# NT1066_Discovery.net
KiCad netlist of a schematic drawn in EAGLE
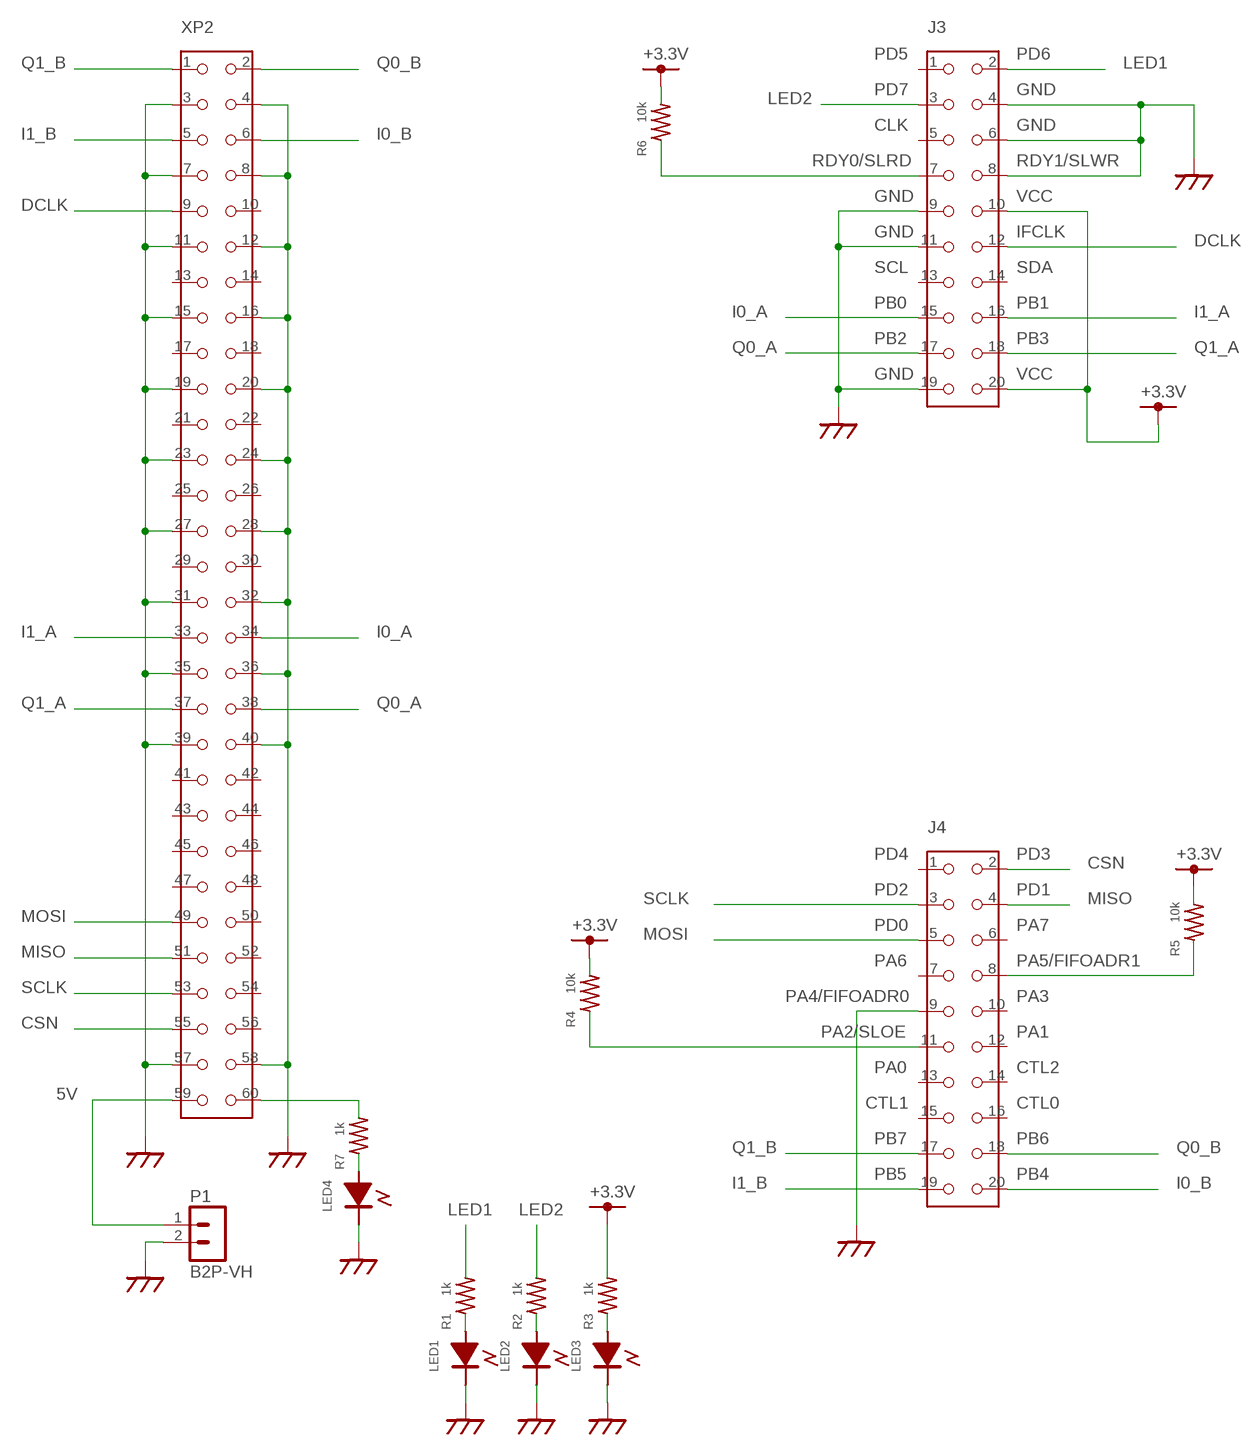
[diagram p0: schematic, sheet 1]

(export (version "E")
  (design (tool "Eeschema 10.0.6"))
  (components
    (comp (ref "J3")
      (value "PINH-2.54MM-20P")
      (footprint "eagle-import:PINH-2.54MM-20P")
      (libsource (lib "eagle-import") (part "PINH-2.54MM-20P"))
    )
    (comp (ref "J4")
      (value "PINH-2.54MM-20P")
      (footprint "eagle-import:PINH-2.54MM-20P")
      (libsource (lib "eagle-import") (part "PINH-2.54MM-20P"))
    )
    (comp (ref "LED1")
      (value "LED1608")
      (footprint "eagle-import:LED_1608")
      (libsource (lib "eagle-import") (part "LED1608"))
    )
    (comp (ref "LED2")
      (value "LED1608")
      (footprint "eagle-import:LED_1608")
      (libsource (lib "eagle-import") (part "LED1608"))
    )
    (comp (ref "LED3")
      (value "LED1608")
      (footprint "eagle-import:LED_1608")
      (libsource (lib "eagle-import") (part "LED1608"))
    )
    (comp (ref "LED4")
      (value "LED1608")
      (footprint "eagle-import:LED_1608")
      (libsource (lib "eagle-import") (part "LED1608"))
    )
    (comp (ref "P1")
      (value "B2P-VH")
      (footprint "eagle-import:B2P-VH")
      (libsource (lib "eagle-import") (part "B2P-VH"))
    )
    (comp (ref "R1")
      (value "1k")
      (footprint "eagle-import:C1608")
      (libsource (lib "eagle-import") (part "R1608"))
    )
    (comp (ref "R2")
      (value "1k")
      (footprint "eagle-import:C1608")
      (libsource (lib "eagle-import") (part "R1608"))
    )
    (comp (ref "R3")
      (value "1k")
      (footprint "eagle-import:C1608")
      (libsource (lib "eagle-import") (part "R1608"))
    )
    (comp (ref "R4")
      (value "10k")
      (footprint "eagle-import:C1608")
      (libsource (lib "eagle-import") (part "R1608"))
    )
    (comp (ref "R5")
      (value "10k")
      (footprint "eagle-import:C1608")
      (libsource (lib "eagle-import") (part "R1608"))
    )
    (comp (ref "R6")
      (value "10k")
      (footprint "eagle-import:C1608")
      (libsource (lib "eagle-import") (part "R1608"))
    )
    (comp (ref "R7")
      (value "1k")
      (footprint "eagle-import:C1608")
      (libsource (lib "eagle-import") (part "R1608"))
    )
    (comp (ref "XP2")
      (value "PINH-2.54MM-60P")
      (footprint "eagle-import:PINH-2.54MM-60P")
      (libsource (lib "eagle-import") (part "PINH-2.54MM-60P"))
    )
  )
  (nets
    (net (code "1") (name "+3.3V") (class "Default")
      (node (ref "J3") (pin "10") (pinfunction "P10_10") (pintype "bidirectional"))
      (node (ref "J3") (pin "20") (pinfunction "P20_20") (pintype "bidirectional"))
      (node (ref "R3") (pin "2") (pinfunction "P$2_2") (pintype "passive"))
      (node (ref "R4") (pin "2") (pinfunction "P$2_2") (pintype "passive"))
      (node (ref "R5") (pin "2") (pinfunction "P$2_2") (pintype "passive"))
      (node (ref "R6") (pin "2") (pinfunction "P$2_2") (pintype "passive"))
    )
    (net (code "2") (name "/5V") (class "Default")
      (node (ref "P1") (pin "1") (pinfunction "1_1") (pintype "passive"))
      (node (ref "XP2") (pin "59") (pinfunction "P59_59") (pintype "bidirectional"))
    )
    (net (code "3") (name "/CSN") (class "Default")
      (node (ref "J4") (pin "2") (pinfunction "P2_2") (pintype "bidirectional"))
      (node (ref "XP2") (pin "55") (pinfunction "P55_55") (pintype "bidirectional"))
    )
    (net (code "4") (name "/DCLK") (class "Default")
      (node (ref "J3") (pin "12") (pinfunction "P12_12") (pintype "bidirectional"))
      (node (ref "XP2") (pin "9") (pinfunction "P9_9") (pintype "bidirectional"))
    )
    (net (code "5") (name "/I0_A") (class "Default")
      (node (ref "J3") (pin "15") (pinfunction "P15_15") (pintype "bidirectional"))
      (node (ref "XP2") (pin "34") (pinfunction "P34_34") (pintype "bidirectional"))
    )
    (net (code "6") (name "/I0_B") (class "Default")
      (node (ref "J4") (pin "20") (pinfunction "P20_20") (pintype "bidirectional"))
      (node (ref "XP2") (pin "6") (pinfunction "P6_6") (pintype "bidirectional"))
    )
    (net (code "7") (name "/I1_A") (class "Default")
      (node (ref "J3") (pin "16") (pinfunction "P16_16") (pintype "bidirectional"))
      (node (ref "XP2") (pin "33") (pinfunction "P33_33") (pintype "bidirectional"))
    )
    (net (code "8") (name "/I1_B") (class "Default")
      (node (ref "J4") (pin "19") (pinfunction "P19_19") (pintype "bidirectional"))
      (node (ref "XP2") (pin "5") (pinfunction "P5_5") (pintype "bidirectional"))
    )
    (net (code "9") (name "/LED1") (class "Default")
      (node (ref "J3") (pin "2") (pinfunction "P2_2") (pintype "bidirectional"))
      (node (ref "R1") (pin "2") (pinfunction "P$2_2") (pintype "passive"))
    )
    (net (code "10") (name "/LED2") (class "Default")
      (node (ref "J3") (pin "3") (pinfunction "P3_3") (pintype "bidirectional"))
      (node (ref "R2") (pin "2") (pinfunction "P$2_2") (pintype "passive"))
    )
    (net (code "11") (name "/MISO") (class "Default")
      (node (ref "J4") (pin "4") (pinfunction "P4_4") (pintype "bidirectional"))
      (node (ref "XP2") (pin "51") (pinfunction "P51_51") (pintype "bidirectional"))
    )
    (net (code "12") (name "/MOSI") (class "Default")
      (node (ref "J4") (pin "5") (pinfunction "P5_5") (pintype "bidirectional"))
      (node (ref "XP2") (pin "49") (pinfunction "P49_49") (pintype "bidirectional"))
    )
    (net (code "13") (name "/Q0_A") (class "Default")
      (node (ref "J3") (pin "17") (pinfunction "P17_17") (pintype "bidirectional"))
      (node (ref "XP2") (pin "38") (pinfunction "P38_38") (pintype "bidirectional"))
    )
    (net (code "14") (name "/Q0_B") (class "Default")
      (node (ref "J4") (pin "18") (pinfunction "P18_18") (pintype "bidirectional"))
      (node (ref "XP2") (pin "2") (pinfunction "P2_2") (pintype "bidirectional"))
    )
    (net (code "15") (name "/Q1_A") (class "Default")
      (node (ref "J3") (pin "18") (pinfunction "P18_18") (pintype "bidirectional"))
      (node (ref "XP2") (pin "37") (pinfunction "P37_37") (pintype "bidirectional"))
    )
    (net (code "16") (name "/Q1_B") (class "Default")
      (node (ref "J4") (pin "17") (pinfunction "P17_17") (pintype "bidirectional"))
      (node (ref "XP2") (pin "1") (pinfunction "P1_1") (pintype "bidirectional"))
    )
    (net (code "17") (name "/SCLK") (class "Default")
      (node (ref "J4") (pin "3") (pinfunction "P3_3") (pintype "bidirectional"))
      (node (ref "XP2") (pin "53") (pinfunction "P53_53") (pintype "bidirectional"))
    )
    (net (code "18") (name "GND") (class "Default")
      (node (ref "J3") (pin "11") (pinfunction "P11_11") (pintype "bidirectional"))
      (node (ref "J3") (pin "19") (pinfunction "P19_19") (pintype "bidirectional"))
      (node (ref "J3") (pin "4") (pinfunction "P4_4") (pintype "bidirectional"))
      (node (ref "J3") (pin "6") (pinfunction "P6_6") (pintype "bidirectional"))
      (node (ref "J3") (pin "8") (pinfunction "P8_8") (pintype "bidirectional"))
      (node (ref "J3") (pin "9") (pinfunction "P9_9") (pintype "bidirectional"))
      (node (ref "J4") (pin "9") (pinfunction "P9_9") (pintype "bidirectional"))
      (node (ref "LED1") (pin "2") (pinfunction "P$2_2") (pintype "passive"))
      (node (ref "LED2") (pin "2") (pinfunction "P$2_2") (pintype "passive"))
      (node (ref "LED3") (pin "2") (pinfunction "P$2_2") (pintype "passive"))
      (node (ref "LED4") (pin "2") (pinfunction "P$2_2") (pintype "passive"))
      (node (ref "P1") (pin "2") (pinfunction "2_2") (pintype "passive"))
      (node (ref "XP2") (pin "11") (pinfunction "P11_11") (pintype "bidirectional"))
      (node (ref "XP2") (pin "12") (pinfunction "P12_12") (pintype "bidirectional"))
      (node (ref "XP2") (pin "15") (pinfunction "P15_15") (pintype "bidirectional"))
      (node (ref "XP2") (pin "16") (pinfunction "P16_16") (pintype "bidirectional"))
      (node (ref "XP2") (pin "19") (pinfunction "P19_19") (pintype "bidirectional"))
      (node (ref "XP2") (pin "20") (pinfunction "P20_20") (pintype "bidirectional"))
      (node (ref "XP2") (pin "23") (pinfunction "P23_23") (pintype "bidirectional"))
      (node (ref "XP2") (pin "24") (pinfunction "P24_24") (pintype "bidirectional"))
      (node (ref "XP2") (pin "27") (pinfunction "P27_27") (pintype "bidirectional"))
      (node (ref "XP2") (pin "28") (pinfunction "P28_28") (pintype "bidirectional"))
      (node (ref "XP2") (pin "3") (pinfunction "P3_3") (pintype "bidirectional"))
      (node (ref "XP2") (pin "31") (pinfunction "P31_31") (pintype "bidirectional"))
      (node (ref "XP2") (pin "32") (pinfunction "P32_32") (pintype "bidirectional"))
      (node (ref "XP2") (pin "35") (pinfunction "P35_35") (pintype "bidirectional"))
      (node (ref "XP2") (pin "36") (pinfunction "P36_36") (pintype "bidirectional"))
      (node (ref "XP2") (pin "39") (pinfunction "P39_39") (pintype "bidirectional"))
      (node (ref "XP2") (pin "4") (pinfunction "P4_4") (pintype "bidirectional"))
      (node (ref "XP2") (pin "40") (pinfunction "P40_40") (pintype "bidirectional"))
      (node (ref "XP2") (pin "57") (pinfunction "P57_57") (pintype "bidirectional"))
      (node (ref "XP2") (pin "58") (pinfunction "P58_58") (pintype "bidirectional"))
      (node (ref "XP2") (pin "7") (pinfunction "P7_7") (pintype "bidirectional"))
      (node (ref "XP2") (pin "8") (pinfunction "P8_8") (pintype "bidirectional"))
    )
    (net (code "19") (name "Net-(J3-P7)") (class "Default")
      (node (ref "J3") (pin "7") (pinfunction "P7_7") (pintype "bidirectional"))
      (node (ref "R6") (pin "1") (pinfunction "P$1_1") (pintype "passive"))
    )
    (net (code "20") (name "Net-(J4-P8)") (class "Default")
      (node (ref "J4") (pin "8") (pinfunction "P8_8") (pintype "bidirectional"))
      (node (ref "R5") (pin "1") (pinfunction "P$1_1") (pintype "passive"))
    )
    (net (code "21") (name "Net-(J4-P11)") (class "Default")
      (node (ref "J4") (pin "11") (pinfunction "P11_11") (pintype "bidirectional"))
      (node (ref "R4") (pin "1") (pinfunction "P$1_1") (pintype "passive"))
    )
    (net (code "22") (name "Net-(LED1-+)") (class "Default")
      (node (ref "LED1") (pin "1") (pinfunction "+_1") (pintype "passive"))
      (node (ref "R1") (pin "1") (pinfunction "P$1_1") (pintype "passive"))
    )
    (net (code "23") (name "Net-(LED2-+)") (class "Default")
      (node (ref "LED2") (pin "1") (pinfunction "+_1") (pintype "passive"))
      (node (ref "R2") (pin "1") (pinfunction "P$1_1") (pintype "passive"))
    )
    (net (code "24") (name "Net-(LED3-+)") (class "Default")
      (node (ref "LED3") (pin "1") (pinfunction "+_1") (pintype "passive"))
      (node (ref "R3") (pin "1") (pinfunction "P$1_1") (pintype "passive"))
    )
    (net (code "25") (name "Net-(LED4-+)") (class "Default")
      (node (ref "LED4") (pin "1") (pinfunction "+_1") (pintype "passive"))
      (node (ref "R7") (pin "1") (pinfunction "P$1_1") (pintype "passive"))
    )
    (net (code "26") (name "Net-(R7-P$2)") (class "Default")
      (node (ref "R7") (pin "2") (pinfunction "P$2_2") (pintype "passive"))
      (node (ref "XP2") (pin "60") (pinfunction "P60_60") (pintype "bidirectional"))
    )
    (net (code "27") (name "unconnected-(J3-P1-Pad1)") (class "Default")
      (node (ref "J3") (pin "1") (pinfunction "P1_1") (pintype "bidirectional"))
    )
    (net (code "28") (name "unconnected-(J3-P5-Pad5)") (class "Default")
      (node (ref "J3") (pin "5") (pinfunction "P5_5") (pintype "bidirectional"))
    )
    (net (code "29") (name "unconnected-(J3-P13-Pad13)") (class "Default")
      (node (ref "J3") (pin "13") (pinfunction "P13_13") (pintype "bidirectional"))
    )
    (net (code "30") (name "unconnected-(J3-P14-Pad14)") (class "Default")
      (node (ref "J3") (pin "14") (pinfunction "P14_14") (pintype "bidirectional"))
    )
    (net (code "31") (name "unconnected-(J4-P1-Pad1)") (class "Default")
      (node (ref "J4") (pin "1") (pinfunction "P1_1") (pintype "bidirectional"))
    )
    (net (code "32") (name "unconnected-(J4-P6-Pad6)") (class "Default")
      (node (ref "J4") (pin "6") (pinfunction "P6_6") (pintype "bidirectional"))
    )
    (net (code "33") (name "unconnected-(J4-P7-Pad7)") (class "Default")
      (node (ref "J4") (pin "7") (pinfunction "P7_7") (pintype "bidirectional"))
    )
    (net (code "34") (name "unconnected-(J4-P10-Pad10)") (class "Default")
      (node (ref "J4") (pin "10") (pinfunction "P10_10") (pintype "bidirectional"))
    )
    (net (code "35") (name "unconnected-(J4-P12-Pad12)") (class "Default")
      (node (ref "J4") (pin "12") (pinfunction "P12_12") (pintype "bidirectional"))
    )
    (net (code "36") (name "unconnected-(J4-P13-Pad13)") (class "Default")
      (node (ref "J4") (pin "13") (pinfunction "P13_13") (pintype "bidirectional"))
    )
    (net (code "37") (name "unconnected-(J4-P14-Pad14)") (class "Default")
      (node (ref "J4") (pin "14") (pinfunction "P14_14") (pintype "bidirectional"))
    )
    (net (code "38") (name "unconnected-(J4-P15-Pad15)") (class "Default")
      (node (ref "J4") (pin "15") (pinfunction "P15_15") (pintype "bidirectional"))
    )
    (net (code "39") (name "unconnected-(J4-P16-Pad16)") (class "Default")
      (node (ref "J4") (pin "16") (pinfunction "P16_16") (pintype "bidirectional"))
    )
    (net (code "40") (name "unconnected-(XP2-P10-Pad10)") (class "Default")
      (node (ref "XP2") (pin "10") (pinfunction "P10_10") (pintype "bidirectional"))
    )
    (net (code "41") (name "unconnected-(XP2-P13-Pad13)") (class "Default")
      (node (ref "XP2") (pin "13") (pinfunction "P13_13") (pintype "bidirectional"))
    )
    (net (code "42") (name "unconnected-(XP2-P14-Pad14)") (class "Default")
      (node (ref "XP2") (pin "14") (pinfunction "P14_14") (pintype "bidirectional"))
    )
    (net (code "43") (name "unconnected-(XP2-P17-Pad17)") (class "Default")
      (node (ref "XP2") (pin "17") (pinfunction "P17_17") (pintype "bidirectional"))
    )
    (net (code "44") (name "unconnected-(XP2-P18-Pad18)") (class "Default")
      (node (ref "XP2") (pin "18") (pinfunction "P18_18") (pintype "bidirectional"))
    )
    (net (code "45") (name "unconnected-(XP2-P21-Pad21)") (class "Default")
      (node (ref "XP2") (pin "21") (pinfunction "P21_21") (pintype "bidirectional"))
    )
    (net (code "46") (name "unconnected-(XP2-P22-Pad22)") (class "Default")
      (node (ref "XP2") (pin "22") (pinfunction "P22_22") (pintype "bidirectional"))
    )
    (net (code "47") (name "unconnected-(XP2-P25-Pad25)") (class "Default")
      (node (ref "XP2") (pin "25") (pinfunction "P25_25") (pintype "bidirectional"))
    )
    (net (code "48") (name "unconnected-(XP2-P26-Pad26)") (class "Default")
      (node (ref "XP2") (pin "26") (pinfunction "P26_26") (pintype "bidirectional"))
    )
    (net (code "49") (name "unconnected-(XP2-P29-Pad29)") (class "Default")
      (node (ref "XP2") (pin "29") (pinfunction "P29_29") (pintype "bidirectional"))
    )
    (net (code "50") (name "unconnected-(XP2-P30-Pad30)") (class "Default")
      (node (ref "XP2") (pin "30") (pinfunction "P30_30") (pintype "bidirectional"))
    )
    (net (code "51") (name "unconnected-(XP2-P41-Pad41)") (class "Default")
      (node (ref "XP2") (pin "41") (pinfunction "P41_41") (pintype "bidirectional"))
    )
    (net (code "52") (name "unconnected-(XP2-P42-Pad42)") (class "Default")
      (node (ref "XP2") (pin "42") (pinfunction "P42_42") (pintype "bidirectional"))
    )
    (net (code "53") (name "unconnected-(XP2-P43-Pad43)") (class "Default")
      (node (ref "XP2") (pin "43") (pinfunction "P43_43") (pintype "bidirectional"))
    )
    (net (code "54") (name "unconnected-(XP2-P44-Pad44)") (class "Default")
      (node (ref "XP2") (pin "44") (pinfunction "P44_44") (pintype "bidirectional"))
    )
    (net (code "55") (name "unconnected-(XP2-P45-Pad45)") (class "Default")
      (node (ref "XP2") (pin "45") (pinfunction "P45_45") (pintype "bidirectional"))
    )
    (net (code "56") (name "unconnected-(XP2-P46-Pad46)") (class "Default")
      (node (ref "XP2") (pin "46") (pinfunction "P46_46") (pintype "bidirectional"))
    )
    (net (code "57") (name "unconnected-(XP2-P47-Pad47)") (class "Default")
      (node (ref "XP2") (pin "47") (pinfunction "P47_47") (pintype "bidirectional"))
    )
    (net (code "58") (name "unconnected-(XP2-P48-Pad48)") (class "Default")
      (node (ref "XP2") (pin "48") (pinfunction "P48_48") (pintype "bidirectional"))
    )
    (net (code "59") (name "unconnected-(XP2-P50-Pad50)") (class "Default")
      (node (ref "XP2") (pin "50") (pinfunction "P50_50") (pintype "bidirectional"))
    )
    (net (code "60") (name "unconnected-(XP2-P52-Pad52)") (class "Default")
      (node (ref "XP2") (pin "52") (pinfunction "P52_52") (pintype "bidirectional"))
    )
    (net (code "61") (name "unconnected-(XP2-P54-Pad54)") (class "Default")
      (node (ref "XP2") (pin "54") (pinfunction "P54_54") (pintype "bidirectional"))
    )
    (net (code "62") (name "unconnected-(XP2-P56-Pad56)") (class "Default")
      (node (ref "XP2") (pin "56") (pinfunction "P56_56") (pintype "bidirectional"))
    )
  )
)
